# ProDocument_FAB-O-MATIC_2024-05-17.net
KiCad netlist of a schematic drawn in EasyEDA Pro
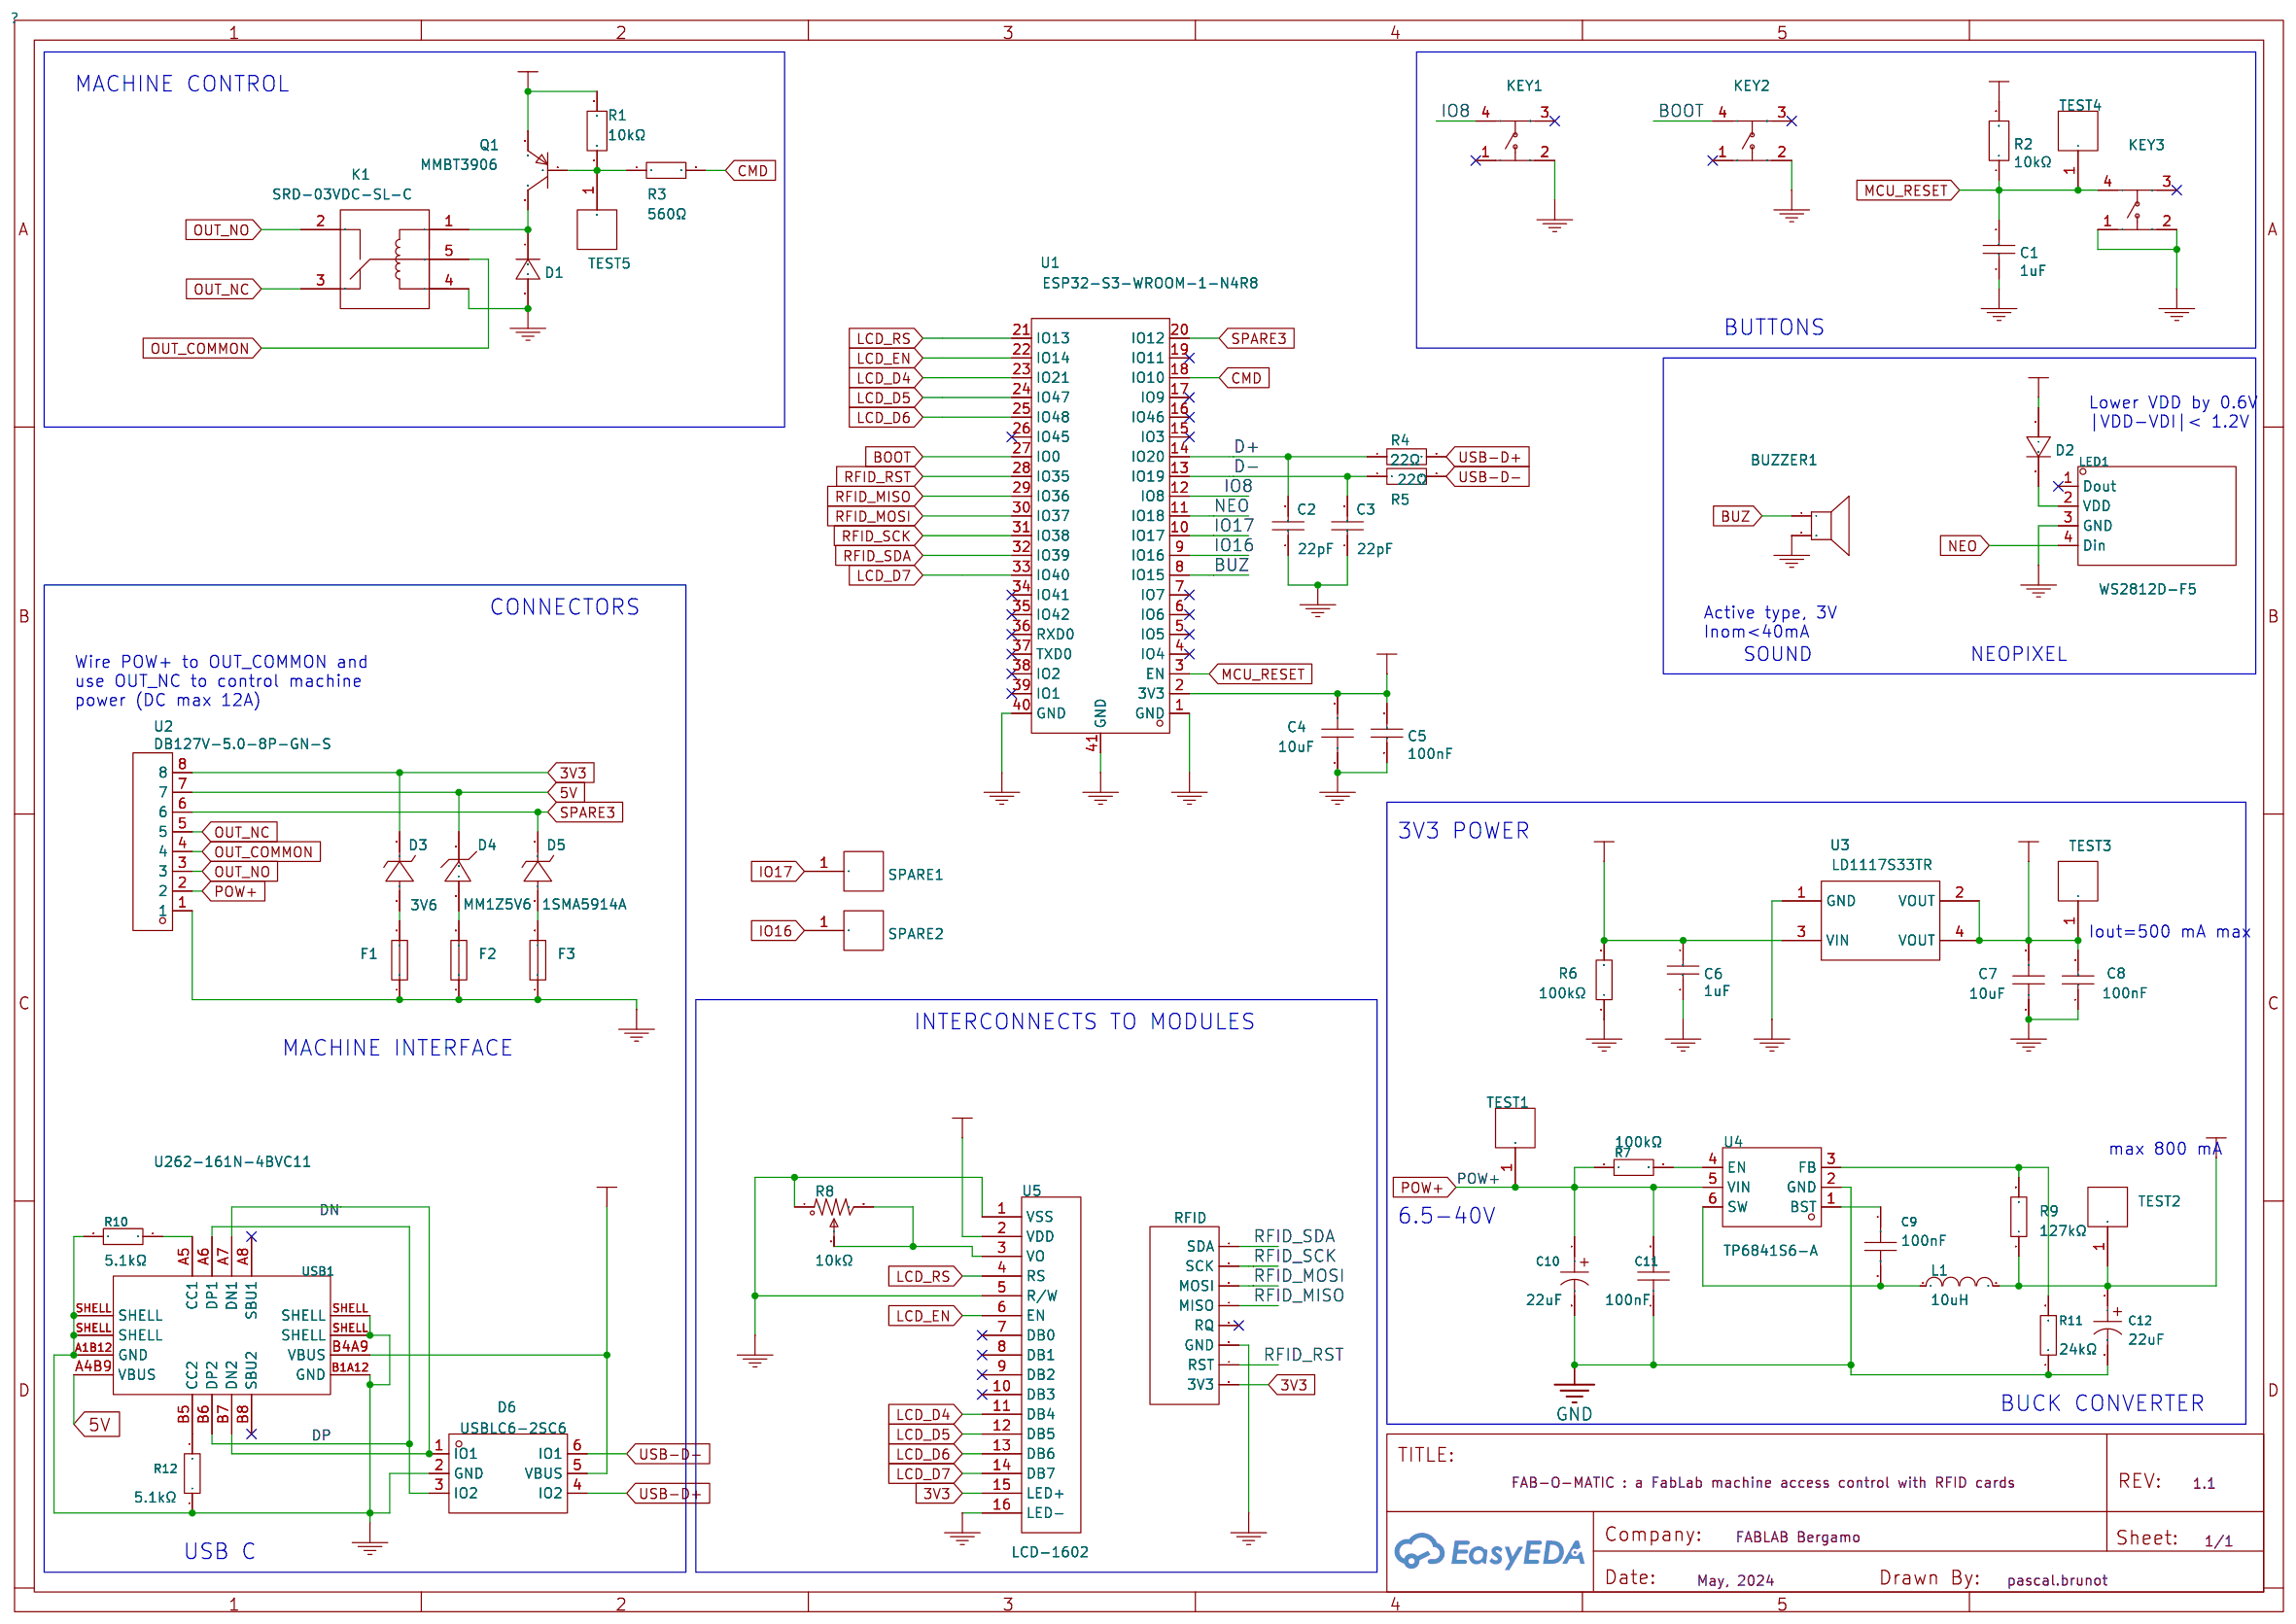
[diagram p0: Schematics]
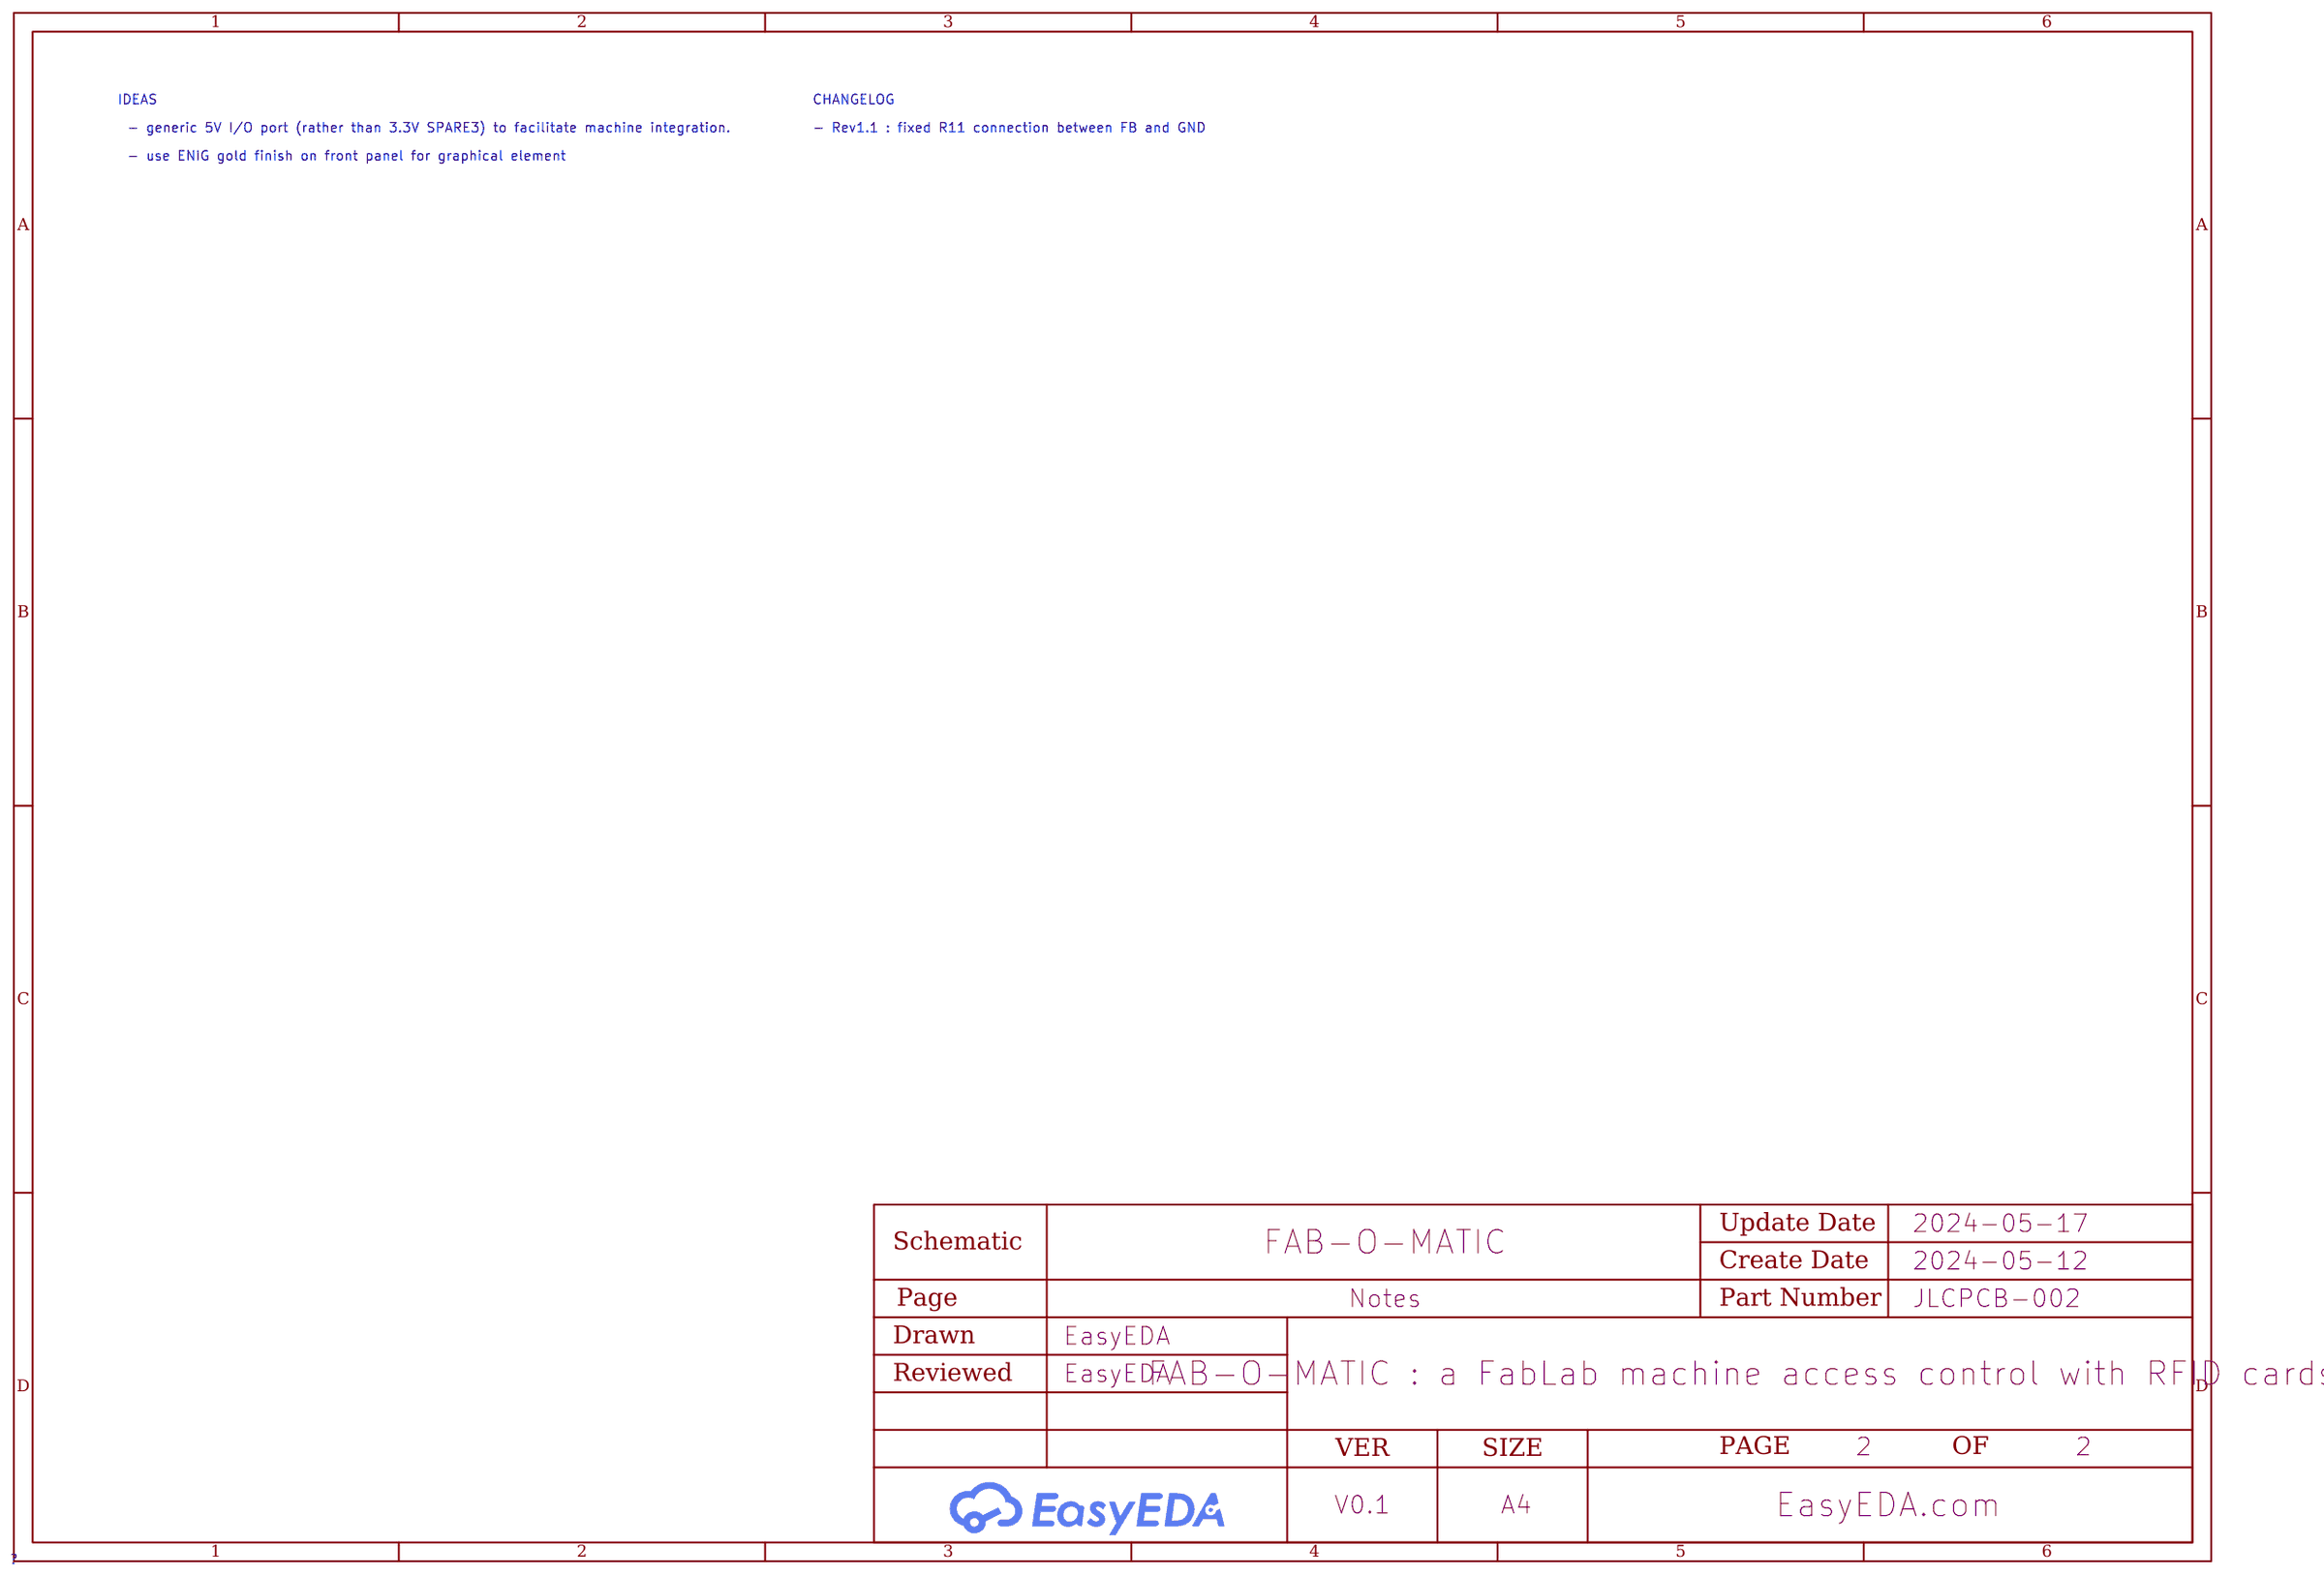
[diagram p1: Notes]

(export (version "E")
  (design (tool "Eeschema 10.0.6"))
  (components
    (comp (ref "BUZZER1")
      (value "4kHz")
      (fields (field (name "Manufacturer Part") "SFN-12055PA6.5") (field (name "Manufacturer") "S&S(海旭)"))
      (libsource (lib "easyedapro") (part "4000Hz"))
    )
    (comp (ref "C1")
      (value "1uF")
      (fields
        (field (name "Manufacturer Part") "CL21B105KBFNNNE")
        (field (name "Manufacturer") "SAMSUNG(三星)")
      )
      (libsource (lib "easyedapro") (part "1uF"))
    )
    (comp (ref "C2")
      (value "22pF")
      (fields
        (field (name "Manufacturer Part") "CL10C220JB8NNNC")
        (field (name "Manufacturer") "SAMSUNG(三星)")
      )
      (libsource (lib "easyedapro") (part "22pF"))
    )
    (comp (ref "C3")
      (value "22pF")
      (fields
        (field (name "Manufacturer Part") "CL10C220JB8NNNC")
        (field (name "Manufacturer") "SAMSUNG(三星)")
      )
      (libsource (lib "easyedapro") (part "22pF"))
    )
    (comp (ref "C4")
      (value "10uF")
      (fields
        (field (name "Manufacturer Part") "GRM21BR61H106KE43L")
        (field (name "Manufacturer") "muRata(村田)")
      )
      (libsource (lib "easyedapro") (part "10uF"))
    )
    (comp (ref "C5")
      (value "100nF")
      (fields
        (field (name "Manufacturer Part") "CL21B104KCFNNNE")
        (field (name "Manufacturer") "SAMSUNG(三星)")
      )
      (libsource (lib "easyedapro") (part "100nF"))
    )
    (comp (ref "C6")
      (value "1uF")
      (fields
        (field (name "Manufacturer Part") "CL21B105KBFNNNE")
        (field (name "Manufacturer") "SAMSUNG(三星)")
      )
      (libsource (lib "easyedapro") (part "1uF"))
    )
    (comp (ref "C7")
      (value "10uF")
      (fields
        (field (name "Manufacturer Part") "GRM21BR61H106KE43L")
        (field (name "Manufacturer") "muRata(村田)")
      )
      (libsource (lib "easyedapro") (part "10uF"))
    )
    (comp (ref "C8")
      (value "100nF")
      (fields
        (field (name "Manufacturer Part") "CL21B104KCFNNNE")
        (field (name "Manufacturer") "SAMSUNG(三星)")
      )
      (libsource (lib "easyedapro") (part "100nF"))
    )
    (comp (ref "C9")
      (value "100nF")
      (footprint "easyedapro:C0603")
      (fields
        (field (name "Manufacturer Part") "CC0603KRX7R9BB104")
        (field (name "Manufacturer") "YAGEO(国巨)")
      )
      (libsource (lib "easyedapro") (part "CC0603KRX7R9BB104"))
    )
    (comp (ref "C10")
      (value "22uF")
      (footprint "easyedapro:CAP-SMD_BD6.3-L6.6-W6.6-FD")
      (fields
        (field (name "Manufacturer Part") "RVT22UF50V67RV0028")
        (field (name "Manufacturer") "KNSCHA(科尼盛)")
      )
      (libsource (lib "easyedapro") (part "RVT22UF50V67RV0028"))
    )
    (comp (ref "C11")
      (value "100nF")
      (footprint "easyedapro:C0603")
      (fields
        (field (name "Manufacturer Part") "CC0603KRX7R9BB104")
        (field (name "Manufacturer") "YAGEO(国巨)")
      )
      (libsource (lib "easyedapro") (part "CC0603KRX7R9BB104"))
    )
    (comp (ref "C12")
      (value "22uF")
      (footprint "easyedapro:CAP-SMD_BD6.3-L6.6-W6.6-FD")
      (fields
        (field (name "Manufacturer Part") "RVT22UF50V67RV0028")
        (field (name "Manufacturer") "KNSCHA(科尼盛)")
      )
      (libsource (lib "easyedapro") (part "RVT22UF50V67RV0028"))
    )
    (comp (ref "D1")
      (value "SM4007PL")
      (fields (field (name "Manufacturer") "MDD"))
      (libsource (lib "easyedapro") (part "SM4007PL"))
    )
    (comp (ref "D2")
      (value "SM4007PL")
      (fields (field (name "Manufacturer") "MDD"))
      (libsource (lib "easyedapro") (part "SM4007PL"))
    )
    (comp (ref "D3")
      (value "3V6")
      (fields (field (name "Manufacturer") "LGE(鲁光)"))
      (libsource (lib "easyedapro") (part "3V6"))
    )
    (comp (ref "D4")
      (value "MM1Z5V6")
      (fields (field (name "Manufacturer") "ST(先科)"))
      (libsource (lib "easyedapro") (part "5V6"))
    )
    (comp (ref "D5")
      (value "1SMA5914A")
      (fields (field (name "Manufacturer") "LGE(鲁光)"))
      (libsource (lib "easyedapro") (part "3V6"))
    )
    (comp (ref "D6")
      (value "USBLC6-2SC6")
      (fields (field (name "Manufacturer") "TECH PUBLIC(台舟)"))
      (libsource (lib "easyedapro") (part "USBLC6"))
    )
    (comp (ref "F1")
      (value "1206L016WR")
      (fields (field (name "Manufacturer") "Littelfuse(美国力特)"))
      (libsource (lib "easyedapro") (part "1206L016WR"))
    )
    (comp (ref "F2")
      (value "1206L016WR")
      (fields (field (name "Manufacturer") "Littelfuse(美国力特)"))
      (libsource (lib "easyedapro") (part "1206L016WR"))
    )
    (comp (ref "F3")
      (value "1206L016WR")
      (fields (field (name "Manufacturer") "Littelfuse(美国力特)"))
      (libsource (lib "easyedapro") (part "1206L016WR"))
    )
    (comp (ref "K1")
      (value "SRD-03VDC-SL-C")
      (fields (field (name "Manufacturer") "松乐"))
      (libsource (lib "easyedapro") (part "SRD-03VDC-SL-C_C496430"))
    )
    (comp (ref "KEY1")
      (value "TSA063G60-250")
      (footprint "easyedapro:KEY-SMD_4P-L6.1-W6.1-P4.50-LS9.0")
      (fields (field (name "Manufacturer") "BRIGHT(博瑞泰)"))
      (libsource (lib "easyedapro") (part "TSA063G60-250"))
    )
    (comp (ref "KEY2")
      (value "TSA063G60-250")
      (footprint "easyedapro:KEY-SMD_4P-L6.1-W6.1-P4.50-LS9.0")
      (fields (field (name "Manufacturer") "BRIGHT(博瑞泰)"))
      (libsource (lib "easyedapro") (part "TSA063G60-250"))
    )
    (comp (ref "KEY3")
      (value "TSA063G60-250")
      (footprint "easyedapro:KEY-SMD_4P-L6.1-W6.1-P4.50-LS9.0")
      (fields (field (name "Manufacturer") "BRIGHT(博瑞泰)"))
      (libsource (lib "easyedapro") (part "TSA063G60-250"))
    )
    (comp (ref "L1")
      (value "10uH")
      (footprint "easyedapro:IND-SMD_L4.0-W4.0")
      (fields (field (name "Manufacturer Part") "SWPA4030S100MT") (field (name "Manufacturer") "Sunlord(顺络)"))
      (libsource (lib "easyedapro") (part "SWPA4030S100MT"))
    )
    (comp (ref "LED1")
      (value "WS2812D-F5")
      (footprint "easyedapro:LED-TH_4P-BD5.8-P1.30")
      (description "Lamp Holder Type:5mm圆形灯头")
      (fields (field (name "Manufacturer") "worldsemi"))
      (libsource (lib "easyedapro") (part "WS2812D-F5"))
    )
    (comp (ref "P1")
      (value "RFID")
      (footprint "easyedapro:footprint_17af")
      (fields
        (field (name "Manufacturer Part") "Female headerHDR1X8-2.54")
        (field (name "Manufacturer") "BOOMELE")
      )
      (libsource (lib "easyedapro") (part "RFID"))
    )
    (comp (ref "Q1")
      (value "MMBT3906")
      (fields (field (name "Manufacturer") "High Diode(海德)"))
      (libsource (lib "easyedapro") (part "2N3906-AP"))
    )
    (comp (ref "R1")
      (value "10kΩ")
      (fields
        (field (name "Manufacturer Part") "0805W8F1002T5E")
        (field (name "Manufacturer") "UNI-ROYAL(厚声)")
      )
      (libsource (lib "easyedapro") (part "10k"))
    )
    (comp (ref "R2")
      (value "10kΩ")
      (fields
        (field (name "Manufacturer Part") "0805W8F1002T5E")
        (field (name "Manufacturer") "UNI-ROYAL(厚声)")
      )
      (libsource (lib "easyedapro") (part "10k"))
    )
    (comp (ref "R3")
      (value "560Ω")
      (fields
        (field (name "Manufacturer Part") "0805W8F5600T5E")
        (field (name "Manufacturer") "UNI-ROYAL(厚声)")
      )
      (libsource (lib "easyedapro") (part "560Ω"))
    )
    (comp (ref "R4")
      (value "22Ω")
      (fields
        (field (name "Manufacturer Part") "0603WAF220JT5E")
        (field (name "Manufacturer") "UNI-ROYAL(厚声)")
      )
      (libsource (lib "easyedapro") (part "22"))
    )
    (comp (ref "R5")
      (value "22Ω")
      (fields
        (field (name "Manufacturer Part") "0603WAF220JT5E")
        (field (name "Manufacturer") "UNI-ROYAL(厚声)")
      )
      (libsource (lib "easyedapro") (part "22"))
    )
    (comp (ref "R6")
      (value "100kΩ")
      (fields
        (field (name "Manufacturer Part") "0805W8F1003T5E")
        (field (name "Manufacturer") "UNI-ROYAL(厚声)")
      )
      (libsource (lib "easyedapro") (part "100kΩ"))
    )
    (comp (ref "R7")
      (value "100kΩ")
      (footprint "easyedapro:R0603")
      (fields
        (field (name "Manufacturer Part") "0603WAF1003T5E")
        (field (name "Manufacturer") "UNI-ROYAL(厚声)")
      )
      (libsource (lib "easyedapro") (part "0603WAF1003T5E"))
    )
    (comp (ref "R8")
      (value "10kΩ")
      (footprint "easyedapro:RES-ADJ-TH_3362P")
      (description "Resistance: Tolerance:±10% Tolerance:±10%")
      (fields (field (name "Manufacturer Part") "3362P-1-103") (field (name "Manufacturer") "BOCHEN(博晨)"))
      (libsource (lib "easyedapro") (part "3362P-1-103_C118956"))
    )
    (comp (ref "R9")
      (value "127kΩ")
      (footprint "easyedapro:R0603")
      (fields (field (name "Manufacturer Part") "RC0603FR-07127KL") (field (name "Manufacturer") "YAGEO(国巨)"))
      (libsource (lib "easyedapro") (part "RC0603FR-07127KL"))
    )
    (comp (ref "R10")
      (value "5.1kΩ")
      (footprint "easyedapro:R0603")
      (fields
        (field (name "Manufacturer Part") "0603WAF5101T5E")
        (field (name "Manufacturer") "UNI-ROYAL(厚声)")
      )
      (libsource (lib "easyedapro") (part "0603WAF5101T5E"))
    )
    (comp (ref "R11")
      (value "24kΩ")
      (footprint "easyedapro:R0603")
      (fields
        (field (name "Manufacturer Part") "0603WAF2402T5E")
        (field (name "Manufacturer") "UNI-ROYAL(厚声)")
      )
      (libsource (lib "easyedapro") (part "0603WAF2402T5E"))
    )
    (comp (ref "R12")
      (value "5.1kΩ")
      (footprint "easyedapro:R0603")
      (fields
        (field (name "Manufacturer Part") "0603WAF5101T5E")
        (field (name "Manufacturer") "UNI-ROYAL(厚声)")
      )
      (libsource (lib "easyedapro") (part "0603WAF5101T5E"))
    )
    (comp (ref "SPARE1")
      (value "0577-0-43-80-21-27-10-0")
      (footprint "easyedapro:footprint_662d")
      (libsource (lib "easyedapro") (part "0577-0-43-80-21-27-10-0"))
    )
    (comp (ref "SPARE2")
      (value "0577-0-43-80-21-27-10-0")
      (footprint "easyedapro:footprint_662d")
      (libsource (lib "easyedapro") (part "0577-0-43-80-21-27-10-0"))
    )
    (comp (ref "TEST1")
      (value "0577-0-43-80-21-27-10-0")
      (footprint "easyedapro:footprint_662d")
      (libsource (lib "easyedapro") (part "0577-0-43-80-21-27-10-0"))
    )
    (comp (ref "TEST2")
      (value "0577-0-43-80-21-27-10-0")
      (footprint "easyedapro:footprint_662d")
      (libsource (lib "easyedapro") (part "0577-0-43-80-21-27-10-0"))
    )
    (comp (ref "TEST3")
      (value "0577-0-43-80-21-27-10-0")
      (footprint "easyedapro:footprint_662d")
      (libsource (lib "easyedapro") (part "0577-0-43-80-21-27-10-0"))
    )
    (comp (ref "TEST4")
      (value "0577-0-43-80-21-27-10-0")
      (footprint "easyedapro:footprint_662d")
      (libsource (lib "easyedapro") (part "0577-0-43-80-21-27-10-0"))
    )
    (comp (ref "TEST5")
      (value "0577-0-43-80-21-27-10-0")
      (footprint "easyedapro:footprint_662d")
      (libsource (lib "easyedapro") (part "0577-0-43-80-21-27-10-0"))
    )
    (comp (ref "U1")
      (value "ESP32-S3-WROOM-1-N4R8")
      (fields (field (name "Manufacturer") "ESPRESSIF(乐鑫)"))
      (libsource (lib "easyedapro") (part "ESP32-S3-WROOM-1-N4"))
    )
    (comp (ref "U2")
      (value "DB127V-5.0-8P-GN-S")
      (fields (field (name "Manufacturer") "DORABO(地博电气)"))
      (libsource (lib "easyedapro") (part "DB127V-5.0-8P-GN-S"))
    )
    (comp (ref "U3")
      (value "LD1117S33TR")
      (fields (field (name "Manufacturer") "ST(意法半导体)"))
      (libsource (lib "easyedapro") (part "LD1117S33TR"))
    )
    (comp (ref "U4")
      (value "TP6841S6-A")
      (footprint "easyedapro:SOT-23-6_L2.9-W1.6-P0.95-LS2.8-BL")
      (fields (field (name "Manufacturer") "TECH PUBLIC(台舟)"))
      (libsource (lib "easyedapro") (part "TP6841S6-A"))
    )
    (comp (ref "U5")
      (value "LCD-1602")
      (footprint "easyedapro:footprint_8a57")
      (fields (field (name "Manufacturer Part") "?"))
      (libsource (lib "easyedapro") (part "LCD-1602"))
    )
    (comp (ref "USB1")
      (value "U262-161N-4BVC11")
      (footprint "easyedapro:USB-3.1-SMD_U262-161N-4BVC11")
      (fields (field (name "Manufacturer") "XKB Connectivity(中国星坤)"))
      (libsource (lib "easyedapro") (part "U262-16XN-4BVC11"))
    )
  )
  (nets
    (net (code "1") (name "3V3") (class "Default")
      (node (ref "C4") (pin "2") (pinfunction "2_2") (pintype "unspecified"))
      (node (ref "C5") (pin "2") (pinfunction "2_2") (pintype "input"))
      (node (ref "C7") (pin "2") (pinfunction "2_2") (pintype "unspecified"))
      (node (ref "C8") (pin "2") (pinfunction "2_2") (pintype "input"))
      (node (ref "D3") (pin "1") (pinfunction "C_1") (pintype "unspecified"))
      (node (ref "P1") (pin "8") (pinfunction "3V3_8") (pintype "input"))
      (node (ref "Q1") (pin "1") (pinfunction "1_1") (pintype "input"))
      (node (ref "R1") (pin "2") (pinfunction "2_2") (pintype "unspecified"))
      (node (ref "R2") (pin "2") (pinfunction "2_2") (pintype "unspecified"))
      (node (ref "TEST3") (pin "1") (pinfunction "1_1") (pintype "unspecified"))
      (node (ref "U1") (pin "2") (pinfunction "3V3_2") (pintype "unspecified"))
      (node (ref "U2") (pin "8") (pinfunction "8_8") (pintype "unspecified"))
      (node (ref "U3") (pin "2") (pinfunction "VOUT_2") (pintype "unspecified"))
      (node (ref "U3") (pin "4") (pinfunction "VOUT_4") (pintype "unspecified"))
      (node (ref "U5") (pin "15") (pinfunction "LED+_15") (pintype "unspecified"))
    )
    (net (code "2") (name "5V") (class "Default")
      (node (ref "C12") (pin "1") (pinfunction "1_1") (pintype "input"))
      (node (ref "C6") (pin "1") (pinfunction "1_1") (pintype "input"))
      (node (ref "D2") (pin "2") (pinfunction "A_2") (pintype "unspecified"))
      (node (ref "D4") (pin "1") (pinfunction "C_1") (pintype "unspecified"))
      (node (ref "D6") (pin "5") (pinfunction "VBUS_5") (pintype "unspecified"))
      (node (ref "L1") (pin "2") (pinfunction "2_2") (pintype "input"))
      (node (ref "R6") (pin "2") (pinfunction "2_2") (pintype "unspecified"))
      (node (ref "R9") (pin "1") (pinfunction "1_1") (pintype "unspecified"))
      (node (ref "TEST2") (pin "1") (pinfunction "1_1") (pintype "unspecified"))
      (node (ref "U2") (pin "7") (pinfunction "7_7") (pintype "unspecified"))
      (node (ref "U3") (pin "3") (pinfunction "VIN_3") (pintype "unspecified"))
      (node (ref "U5") (pin "2") (pinfunction "VDD_2") (pintype "unspecified"))
      (node (ref "USB1") (pin "A4B9") (pinfunction "VBUS_A4B9") (pintype "input"))
      (node (ref "USB1") (pin "B4A9") (pinfunction "VBUS_B4A9") (pintype "input"))
    )
    (net (code "3") (name "BOOT") (class "Default")
      (node (ref "KEY2") (pin "4") (pinfunction "4_4") (pintype "input"))
      (node (ref "U1") (pin "27") (pinfunction "IO0_27") (pintype "unspecified"))
    )
    (net (code "4") (name "BUZ") (class "Default")
      (node (ref "BUZZER1") (pin "1") (pinfunction "1_1") (pintype "unspecified"))
      (node (ref "U1") (pin "8") (pinfunction "IO15_8") (pintype "unspecified"))
    )
    (net (code "5") (name "CMD") (class "Default")
      (node (ref "R3") (pin "2") (pinfunction "2_2") (pintype "input"))
      (node (ref "U1") (pin "18") (pinfunction "IO10_18") (pintype "unspecified"))
    )
    (net (code "6") (name "D+") (class "Default")
      (node (ref "C2") (pin "2") (pinfunction "2_2") (pintype "input"))
      (node (ref "R4") (pin "1") (pinfunction "1_1") (pintype "input"))
      (node (ref "U1") (pin "14") (pinfunction "IO20_14") (pintype "unspecified"))
    )
    (net (code "7") (name "D-") (class "Default")
      (node (ref "C3") (pin "2") (pinfunction "2_2") (pintype "input"))
      (node (ref "R5") (pin "1") (pinfunction "1_1") (pintype "input"))
      (node (ref "U1") (pin "13") (pinfunction "IO19_13") (pintype "unspecified"))
    )
    (net (code "8") (name "DN") (class "Default")
      (node (ref "D6") (pin "1") (pinfunction "IO1_1") (pintype "unspecified"))
      (node (ref "USB1") (pin "A7") (pinfunction "DN1_A7") (pintype "input"))
      (node (ref "USB1") (pin "B7") (pinfunction "DN2_B7") (pintype "input"))
    )
    (net (code "9") (name "DP") (class "Default")
      (node (ref "D6") (pin "3") (pinfunction "IO2_3") (pintype "unspecified"))
      (node (ref "USB1") (pin "A6") (pinfunction "DP1_A6") (pintype "input"))
      (node (ref "USB1") (pin "B6") (pinfunction "DP2_B6") (pintype "input"))
    )
    (net (code "10") (name "GND") (class "Default")
      (node (ref "BUZZER1") (pin "2") (pinfunction "2_2") (pintype "unspecified"))
      (node (ref "C1") (pin "1") (pinfunction "1_1") (pintype "input"))
      (node (ref "C10") (pin "2") (pinfunction "2_2") (pintype "input"))
      (node (ref "C11") (pin "1") (pinfunction "1_1") (pintype "input"))
      (node (ref "C12") (pin "2") (pinfunction "2_2") (pintype "input"))
      (node (ref "C2") (pin "1") (pinfunction "1_1") (pintype "input"))
      (node (ref "C3") (pin "1") (pinfunction "1_1") (pintype "input"))
      (node (ref "C4") (pin "1") (pinfunction "1_1") (pintype "unspecified"))
      (node (ref "C5") (pin "1") (pinfunction "1_1") (pintype "input"))
      (node (ref "C6") (pin "2") (pinfunction "2_2") (pintype "input"))
      (node (ref "C7") (pin "1") (pinfunction "1_1") (pintype "unspecified"))
      (node (ref "C8") (pin "1") (pinfunction "1_1") (pintype "input"))
      (node (ref "D1") (pin "2") (pinfunction "A_2") (pintype "unspecified"))
      (node (ref "D6") (pin "2") (pinfunction "GND_2") (pintype "unspecified"))
      (node (ref "F1") (pin "1") (pinfunction "1_1") (pintype "unspecified"))
      (node (ref "F2") (pin "1") (pinfunction "1_1") (pintype "unspecified"))
      (node (ref "F3") (pin "1") (pinfunction "1_1") (pintype "unspecified"))
      (node (ref "K1") (pin "4") (pinfunction "4_4") (pintype "unspecified"))
      (node (ref "KEY1") (pin "2") (pinfunction "2_2") (pintype "input"))
      (node (ref "KEY2") (pin "2") (pinfunction "2_2") (pintype "input"))
      (node (ref "KEY3") (pin "1") (pinfunction "1_1") (pintype "input"))
      (node (ref "KEY3") (pin "2") (pinfunction "2_2") (pintype "input"))
      (node (ref "LED1") (pin "3") (pinfunction "GND_3") (pintype "input"))
      (node (ref "P1") (pin "6") (pinfunction "GND_6") (pintype "input"))
      (node (ref "R10") (pin "2") (pinfunction "2_2") (pintype "input"))
      (node (ref "R11") (pin "1") (pinfunction "1_1") (pintype "input"))
      (node (ref "R12") (pin "1") (pinfunction "1_1") (pintype "input"))
      (node (ref "R6") (pin "1") (pinfunction "1_1") (pintype "unspecified"))
      (node (ref "R8") (pin "1") (pinfunction "1_1") (pintype "input"))
      (node (ref "U1") (pin "1") (pinfunction "GND_1") (pintype "unspecified"))
      (node (ref "U1") (pin "40") (pinfunction "GND_40") (pintype "unspecified"))
      (node (ref "U1") (pin "41") (pinfunction "GND_41") (pintype "unspecified"))
      (node (ref "U2") (pin "1") (pinfunction "1_1") (pintype "unspecified"))
      (node (ref "U3") (pin "1") (pinfunction "GND_1") (pintype "unspecified"))
      (node (ref "U4") (pin "2") (pinfunction "GND_2") (pintype "input"))
      (node (ref "U5") (pin "1") (pinfunction "VSS_1") (pintype "unspecified"))
      (node (ref "U5") (pin "16") (pinfunction "LED-_16") (pintype "unspecified"))
      (node (ref "U5") (pin "5") (pinfunction "R/W_5") (pintype "unspecified"))
      (node (ref "USB1") (pin "A1B12") (pinfunction "GND_A1B12") (pintype "input"))
      (node (ref "USB1") (pin "B1A12") (pinfunction "GND_B1A12") (pintype "input"))
      (node (ref "USB1") (pin "SHELL") (pinfunction "SHELL_SHELL") (pintype "input"))
    )
    (net (code "11") (name "IO8") (class "Default")
      (node (ref "KEY1") (pin "4") (pinfunction "4_4") (pintype "input"))
      (node (ref "U1") (pin "12") (pinfunction "IO8_12") (pintype "unspecified"))
    )
    (net (code "12") (name "IO16") (class "Default")
      (node (ref "SPARE2") (pin "1") (pinfunction "1_1") (pintype "unspecified"))
      (node (ref "U1") (pin "9") (pinfunction "IO16_9") (pintype "unspecified"))
    )
    (net (code "13") (name "IO17") (class "Default")
      (node (ref "SPARE1") (pin "1") (pinfunction "1_1") (pintype "unspecified"))
      (node (ref "U1") (pin "10") (pinfunction "IO17_10") (pintype "unspecified"))
    )
    (net (code "14") (name "LCD_D4") (class "Default")
      (node (ref "U1") (pin "23") (pinfunction "IO21_23") (pintype "unspecified"))
      (node (ref "U5") (pin "11") (pinfunction "DB4_11") (pintype "unspecified"))
    )
    (net (code "15") (name "LCD_D5") (class "Default")
      (node (ref "U1") (pin "24") (pinfunction "IO47_24") (pintype "unspecified"))
      (node (ref "U5") (pin "12") (pinfunction "DB5_12") (pintype "unspecified"))
    )
    (net (code "16") (name "LCD_D6") (class "Default")
      (node (ref "U1") (pin "25") (pinfunction "IO48_25") (pintype "unspecified"))
      (node (ref "U5") (pin "13") (pinfunction "DB6_13") (pintype "unspecified"))
    )
    (net (code "17") (name "LCD_D7") (class "Default")
      (node (ref "U1") (pin "33") (pinfunction "IO40_33") (pintype "unspecified"))
      (node (ref "U5") (pin "14") (pinfunction "DB7_14") (pintype "unspecified"))
    )
    (net (code "18") (name "LCD_EN") (class "Default")
      (node (ref "U1") (pin "22") (pinfunction "IO14_22") (pintype "unspecified"))
      (node (ref "U5") (pin "6") (pinfunction "EN_6") (pintype "unspecified"))
    )
    (net (code "19") (name "LCD_RS") (class "Default")
      (node (ref "U1") (pin "21") (pinfunction "IO13_21") (pintype "unspecified"))
      (node (ref "U5") (pin "4") (pinfunction "RS_4") (pintype "unspecified"))
    )
    (net (code "20") (name "MCU_RESET") (class "Default")
      (node (ref "C1") (pin "2") (pinfunction "2_2") (pintype "input"))
      (node (ref "KEY3") (pin "4") (pinfunction "4_4") (pintype "input"))
      (node (ref "R2") (pin "1") (pinfunction "1_1") (pintype "unspecified"))
      (node (ref "TEST4") (pin "1") (pinfunction "1_1") (pintype "unspecified"))
      (node (ref "U1") (pin "3") (pinfunction "EN_3") (pintype "unspecified"))
    )
    (net (code "21") (name "NEO") (class "Default")
      (node (ref "LED1") (pin "4") (pinfunction "Din_4") (pintype "input"))
      (node (ref "U1") (pin "11") (pinfunction "IO18_11") (pintype "unspecified"))
    )
    (net (code "22") (name "Net-(D1-C)") (class "Default")
      (node (ref "D1") (pin "1") (pinfunction "C_1") (pintype "unspecified"))
      (node (ref "K1") (pin "1") (pinfunction "1_1") (pintype "unspecified"))
      (node (ref "Q1") (pin "3") (pinfunction "3_3") (pintype "input"))
    )
    (net (code "23") (name "Net-(D2-C)") (class "Default")
      (node (ref "D2") (pin "1") (pinfunction "C_1") (pintype "unspecified"))
      (node (ref "LED1") (pin "2") (pinfunction "VDD_2") (pintype "input"))
    )
    (net (code "24") (name "Net-(D3-A)") (class "Default")
      (node (ref "D3") (pin "2") (pinfunction "A_2") (pintype "unspecified"))
      (node (ref "F1") (pin "2") (pinfunction "2_2") (pintype "unspecified"))
    )
    (net (code "25") (name "Net-(D4-A)") (class "Default")
      (node (ref "D4") (pin "2") (pinfunction "A_2") (pintype "unspecified"))
      (node (ref "F2") (pin "2") (pinfunction "2_2") (pintype "unspecified"))
    )
    (net (code "26") (name "Net-(D5-A)") (class "Default")
      (node (ref "D5") (pin "2") (pinfunction "A_2") (pintype "unspecified"))
      (node (ref "F3") (pin "2") (pinfunction "2_2") (pintype "unspecified"))
    )
    (net (code "27") (name "Net-(Q1-Pad2)") (class "Default")
      (node (ref "Q1") (pin "2") (pinfunction "2_2") (pintype "input"))
      (node (ref "R1") (pin "1") (pinfunction "1_1") (pintype "unspecified"))
      (node (ref "R3") (pin "1") (pinfunction "1_1") (pintype "input"))
      (node (ref "TEST5") (pin "1") (pinfunction "1_1") (pintype "unspecified"))
    )
    (net (code "28") (name "Net-(U4-BST)") (class "Default")
      (node (ref "C9") (pin "1") (pinfunction "1_1") (pintype "input"))
      (node (ref "U4") (pin "1") (pinfunction "BST_1") (pintype "input"))
    )
    (net (code "29") (name "Net-(U4-EN)") (class "Default")
      (node (ref "R7") (pin "2") (pinfunction "2_2") (pintype "input"))
      (node (ref "U4") (pin "4") (pinfunction "EN_4") (pintype "input"))
    )
    (net (code "30") (name "Net-(U4-FB)") (class "Default")
      (node (ref "R11") (pin "2") (pinfunction "2_2") (pintype "input"))
      (node (ref "R9") (pin "2") (pinfunction "2_2") (pintype "unspecified"))
      (node (ref "U4") (pin "3") (pinfunction "FB_3") (pintype "input"))
    )
    (net (code "31") (name "Net-(U4-SW)") (class "Default")
      (node (ref "C9") (pin "2") (pinfunction "2_2") (pintype "input"))
      (node (ref "L1") (pin "1") (pinfunction "1_1") (pintype "input"))
      (node (ref "U4") (pin "6") (pinfunction "SW_6") (pintype "input"))
    )
    (net (code "32") (name "Net-(U5-VO)") (class "Default")
      (node (ref "R8") (pin "2") (pinfunction "2_2") (pintype "input"))
      (node (ref "R8") (pin "3") (pinfunction "3_3") (pintype "input"))
      (node (ref "U5") (pin "3") (pinfunction "VO_3") (pintype "unspecified"))
    )
    (net (code "33") (name "Net-(USB1-CC1)") (class "Default")
      (node (ref "R10") (pin "1") (pinfunction "1_1") (pintype "input"))
      (node (ref "USB1") (pin "A5") (pinfunction "CC1_A5") (pintype "input"))
    )
    (net (code "34") (name "Net-(USB1-CC2)") (class "Default")
      (node (ref "R12") (pin "2") (pinfunction "2_2") (pintype "input"))
      (node (ref "USB1") (pin "B5") (pinfunction "CC2_B5") (pintype "input"))
    )
    (net (code "35") (name "OUT_COMMON") (class "Default")
      (node (ref "K1") (pin "5") (pinfunction "5_5") (pintype "unspecified"))
      (node (ref "U2") (pin "4") (pinfunction "4_4") (pintype "unspecified"))
    )
    (net (code "36") (name "OUT_NC") (class "Default")
      (node (ref "K1") (pin "3") (pinfunction "3_3") (pintype "unspecified"))
      (node (ref "U2") (pin "5") (pinfunction "5_5") (pintype "unspecified"))
    )
    (net (code "37") (name "OUT_NO") (class "Default")
      (node (ref "K1") (pin "2") (pinfunction "2_2") (pintype "unspecified"))
      (node (ref "U2") (pin "3") (pinfunction "3_3") (pintype "unspecified"))
    )
    (net (code "38") (name "POW+") (class "Default")
      (node (ref "C10") (pin "1") (pinfunction "1_1") (pintype "input"))
      (node (ref "C11") (pin "2") (pinfunction "2_2") (pintype "input"))
      (node (ref "R7") (pin "1") (pinfunction "1_1") (pintype "input"))
      (node (ref "TEST1") (pin "1") (pinfunction "1_1") (pintype "unspecified"))
      (node (ref "U2") (pin "2") (pinfunction "2_2") (pintype "unspecified"))
      (node (ref "U4") (pin "5") (pinfunction "VIN_5") (pintype "input"))
    )
    (net (code "39") (name "RFID_MISO") (class "Default")
      (node (ref "P1") (pin "4") (pinfunction "MISO_4") (pintype "input"))
      (node (ref "U1") (pin "29") (pinfunction "IO36_29") (pintype "unspecified"))
    )
    (net (code "40") (name "RFID_MOSI") (class "Default")
      (node (ref "P1") (pin "3") (pinfunction "MOSI_3") (pintype "input"))
      (node (ref "U1") (pin "30") (pinfunction "IO37_30") (pintype "unspecified"))
    )
    (net (code "41") (name "RFID_RST") (class "Default")
      (node (ref "P1") (pin "7") (pinfunction "RST_7") (pintype "input"))
      (node (ref "U1") (pin "28") (pinfunction "IO35_28") (pintype "unspecified"))
    )
    (net (code "42") (name "RFID_SCK") (class "Default")
      (node (ref "P1") (pin "2") (pinfunction "SCK_2") (pintype "input"))
      (node (ref "U1") (pin "31") (pinfunction "IO38_31") (pintype "unspecified"))
    )
    (net (code "43") (name "RFID_SDA") (class "Default")
      (node (ref "P1") (pin "1") (pinfunction "SDA_1") (pintype "input"))
      (node (ref "U1") (pin "32") (pinfunction "IO39_32") (pintype "unspecified"))
    )
    (net (code "44") (name "SPARE3") (class "Default")
      (node (ref "D5") (pin "1") (pinfunction "C_1") (pintype "unspecified"))
      (node (ref "U1") (pin "20") (pinfunction "IO12_20") (pintype "unspecified"))
      (node (ref "U2") (pin "6") (pinfunction "6_6") (pintype "unspecified"))
    )
    (net (code "45") (name "USB-D+") (class "Default")
      (node (ref "D6") (pin "4") (pinfunction "IO2_4") (pintype "unspecified"))
      (node (ref "R4") (pin "2") (pinfunction "2_2") (pintype "input"))
    )
    (net (code "46") (name "USB-D-") (class "Default")
      (node (ref "D6") (pin "6") (pinfunction "IO1_6") (pintype "unspecified"))
      (node (ref "R5") (pin "2") (pinfunction "2_2") (pintype "input"))
    )
    (net (code "47") (name "unconnected-(KEY1-Pad1)") (class "Default")
      (node (ref "KEY1") (pin "1") (pinfunction "1_1") (pintype "input+no_connect"))
    )
    (net (code "48") (name "unconnected-(KEY1-Pad3)") (class "Default")
      (node (ref "KEY1") (pin "3") (pinfunction "3_3") (pintype "input+no_connect"))
    )
    (net (code "49") (name "unconnected-(KEY2-Pad1)") (class "Default")
      (node (ref "KEY2") (pin "1") (pinfunction "1_1") (pintype "input+no_connect"))
    )
    (net (code "50") (name "unconnected-(KEY2-Pad3)") (class "Default")
      (node (ref "KEY2") (pin "3") (pinfunction "3_3") (pintype "input+no_connect"))
    )
    (net (code "51") (name "unconnected-(KEY3-Pad3)") (class "Default")
      (node (ref "KEY3") (pin "3") (pinfunction "3_3") (pintype "input+no_connect"))
    )
    (net (code "52") (name "unconnected-(LED1-Dout-Pad1)") (class "Default")
      (node (ref "LED1") (pin "1") (pinfunction "Dout_1") (pintype "input+no_connect"))
    )
    (net (code "53") (name "unconnected-(P1-RQ-Pad5)") (class "Default")
      (node (ref "P1") (pin "5") (pinfunction "RQ_5") (pintype "input+no_connect"))
    )
    (net (code "54") (name "unconnected-(U1-IO1-Pad39)") (class "Default")
      (node (ref "U1") (pin "39") (pinfunction "IO1_39") (pintype "unspecified+no_connect"))
    )
    (net (code "55") (name "unconnected-(U1-IO2-Pad38)") (class "Default")
      (node (ref "U1") (pin "38") (pinfunction "IO2_38") (pintype "unspecified+no_connect"))
    )
    (net (code "56") (name "unconnected-(U1-IO3-Pad15)") (class "Default")
      (node (ref "U1") (pin "15") (pinfunction "IO3_15") (pintype "unspecified+no_connect"))
    )
    (net (code "57") (name "unconnected-(U1-IO4-Pad4)") (class "Default")
      (node (ref "U1") (pin "4") (pinfunction "IO4_4") (pintype "unspecified+no_connect"))
    )
    (net (code "58") (name "unconnected-(U1-IO5-Pad5)") (class "Default")
      (node (ref "U1") (pin "5") (pinfunction "IO5_5") (pintype "unspecified+no_connect"))
    )
    (net (code "59") (name "unconnected-(U1-IO6-Pad6)") (class "Default")
      (node (ref "U1") (pin "6") (pinfunction "IO6_6") (pintype "unspecified+no_connect"))
    )
    (net (code "60") (name "unconnected-(U1-IO7-Pad7)") (class "Default")
      (node (ref "U1") (pin "7") (pinfunction "IO7_7") (pintype "unspecified+no_connect"))
    )
    (net (code "61") (name "unconnected-(U1-IO9-Pad17)") (class "Default")
      (node (ref "U1") (pin "17") (pinfunction "IO9_17") (pintype "unspecified+no_connect"))
    )
    (net (code "62") (name "unconnected-(U1-IO11-Pad19)") (class "Default")
      (node (ref "U1") (pin "19") (pinfunction "IO11_19") (pintype "unspecified+no_connect"))
    )
    (net (code "63") (name "unconnected-(U1-IO41-Pad34)") (class "Default")
      (node (ref "U1") (pin "34") (pinfunction "IO41_34") (pintype "unspecified+no_connect"))
    )
    (net (code "64") (name "unconnected-(U1-IO42-Pad35)") (class "Default")
      (node (ref "U1") (pin "35") (pinfunction "IO42_35") (pintype "unspecified+no_connect"))
    )
    (net (code "65") (name "unconnected-(U1-IO45-Pad26)") (class "Default")
      (node (ref "U1") (pin "26") (pinfunction "IO45_26") (pintype "unspecified+no_connect"))
    )
    (net (code "66") (name "unconnected-(U1-IO46-Pad16)") (class "Default")
      (node (ref "U1") (pin "16") (pinfunction "IO46_16") (pintype "unspecified+no_connect"))
    )
    (net (code "67") (name "unconnected-(U1-RXD0-Pad36)") (class "Default")
      (node (ref "U1") (pin "36") (pinfunction "RXD0_36") (pintype "unspecified+no_connect"))
    )
    (net (code "68") (name "unconnected-(U1-TXD0-Pad37)") (class "Default")
      (node (ref "U1") (pin "37") (pinfunction "TXD0_37") (pintype "unspecified+no_connect"))
    )
    (net (code "69") (name "unconnected-(U5-DB0-Pad7)") (class "Default")
      (node (ref "U5") (pin "7") (pinfunction "DB0_7") (pintype "unspecified+no_connect"))
    )
    (net (code "70") (name "unconnected-(U5-DB1-Pad8)") (class "Default")
      (node (ref "U5") (pin "8") (pinfunction "DB1_8") (pintype "unspecified+no_connect"))
    )
    (net (code "71") (name "unconnected-(U5-DB2-Pad9)") (class "Default")
      (node (ref "U5") (pin "9") (pinfunction "DB2_9") (pintype "unspecified+no_connect"))
    )
    (net (code "72") (name "unconnected-(U5-DB3-Pad10)") (class "Default")
      (node (ref "U5") (pin "10") (pinfunction "DB3_10") (pintype "unspecified+no_connect"))
    )
    (net (code "73") (name "unconnected-(USB1-SBU1-PadA8)") (class "Default")
      (node (ref "USB1") (pin "A8") (pinfunction "SBU1_A8") (pintype "input+no_connect"))
    )
    (net (code "74") (name "unconnected-(USB1-SBU2-PadB8)") (class "Default")
      (node (ref "USB1") (pin "B8") (pinfunction "SBU2_B8") (pintype "input+no_connect"))
    )
  )
)
